# atmega2560_3_3v_8mhz.net
KiCad netlist of a schematic drawn in EAGLE
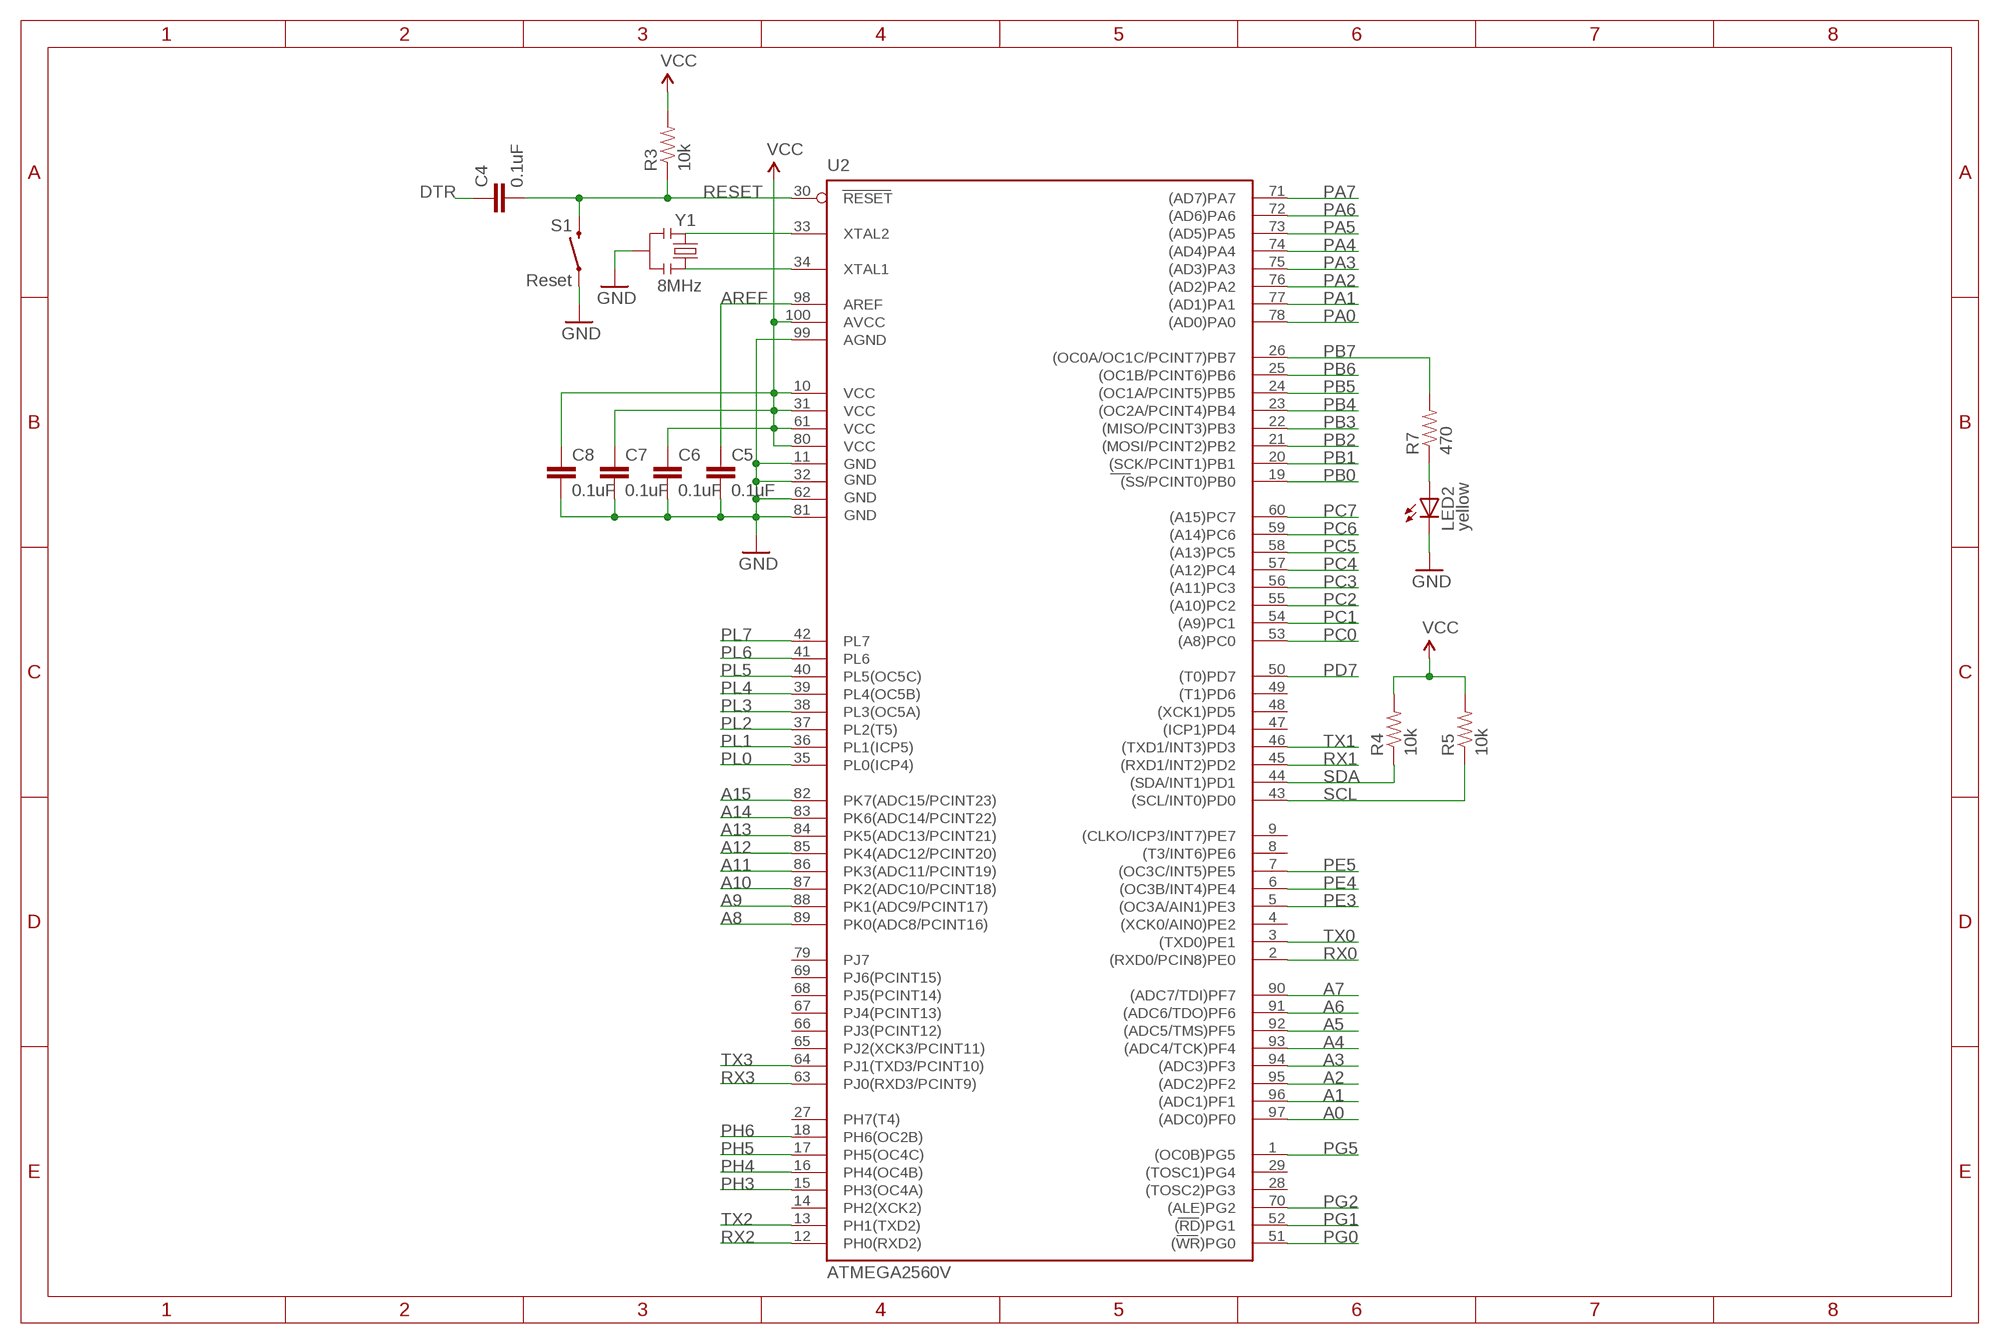
[diagram p0: schematic, sheet 1]

(export (version "E")
  (design (tool "Eeschema 10.0.6"))
  (components
    (comp (ref "C4")
      (value "0.1uF")
      (footprint "eagle-import:0402-CAP")
      (libsource (lib "eagle-import") (part "CAP0402-CAP"))
    )
    (comp (ref "C5")
      (value "0.1uF")
      (footprint "eagle-import:0402-CAP")
      (libsource (lib "eagle-import") (part "CAP0402-CAP"))
    )
    (comp (ref "C6")
      (value "0.1uF")
      (footprint "eagle-import:0402-CAP")
      (libsource (lib "eagle-import") (part "CAP0402-CAP"))
    )
    (comp (ref "C7")
      (value "0.1uF")
      (footprint "eagle-import:0402-CAP")
      (libsource (lib "eagle-import") (part "CAP0402-CAP"))
    )
    (comp (ref "C8")
      (value "0.1uF")
      (footprint "eagle-import:0402-CAP")
      (libsource (lib "eagle-import") (part "CAP0402-CAP"))
    )
    (comp (ref "LED2")
      (value "yellow")
      (footprint "eagle-import:LED-0603")
      (libsource (lib "eagle-import") (part "LED0603"))
    )
    (comp (ref "R3")
      (value "10k")
      (footprint "eagle-import:0402-RES")
      (libsource (lib "eagle-import") (part "RESISTOR0402-RES"))
    )
    (comp (ref "R4")
      (value "10k")
      (footprint "eagle-import:0402-RES")
      (libsource (lib "eagle-import") (part "RESISTOR0402-RES"))
    )
    (comp (ref "R5")
      (value "10k")
      (footprint "eagle-import:0402-RES")
      (libsource (lib "eagle-import") (part "RESISTOR0402-RES"))
    )
    (comp (ref "R7")
      (value "470")
      (footprint "eagle-import:0402-RES")
      (libsource (lib "eagle-import") (part "RESISTOR0402-RES"))
    )
    (comp (ref "S1")
      (value "SWITCH-MOMENTARY-2SMD")
      (footprint "eagle-import:TACTILE_SWITCH_SMD")
      (libsource (lib "eagle-import") (part "SWITCH-MOMENTARY-2SMD"))
    )
    (comp (ref "U2")
      (value "ATMEGA2560AU")
      (footprint "eagle-import:TQFP100")
      (libsource (lib "eagle-import") (part "ATMEGA2560AU"))
    )
    (comp (ref "Y1")
      (value "RESONATORSMD")
      (footprint "eagle-import:RESONATOR-SMD")
      (libsource (lib "eagle-import") (part "RESONATORSMD"))
    )
  )
  (nets
    (net (code "1") (name "/A0") (class "Default")
      (node (ref "U2") (pin "97") (pinfunction "(ADC0)PF0_97") (pintype "bidirectional"))
    )
    (net (code "2") (name "/A1") (class "Default")
      (node (ref "U2") (pin "96") (pinfunction "(ADC1)PF1_96") (pintype "bidirectional"))
    )
    (net (code "3") (name "/A2") (class "Default")
      (node (ref "U2") (pin "95") (pinfunction "(ADC2)PF2_95") (pintype "bidirectional"))
    )
    (net (code "4") (name "/A3") (class "Default")
      (node (ref "U2") (pin "94") (pinfunction "(ADC3)PF3_94") (pintype "bidirectional"))
    )
    (net (code "5") (name "/A4") (class "Default")
      (node (ref "U2") (pin "93") (pinfunction "(ADC4/TCK)PF4_93") (pintype "bidirectional"))
    )
    (net (code "6") (name "/A5") (class "Default")
      (node (ref "U2") (pin "92") (pinfunction "(ADC5/TMS)PF5_92") (pintype "bidirectional"))
    )
    (net (code "7") (name "/A6") (class "Default")
      (node (ref "U2") (pin "91") (pinfunction "(ADC6/TDO)PF6_91") (pintype "bidirectional"))
    )
    (net (code "8") (name "/A7") (class "Default")
      (node (ref "U2") (pin "90") (pinfunction "(ADC7/TDI)PF7_90") (pintype "bidirectional"))
    )
    (net (code "9") (name "/A8") (class "Default")
      (node (ref "U2") (pin "89") (pinfunction "PK0(ADC8/PCINT16)_89") (pintype "bidirectional"))
    )
    (net (code "10") (name "/A9") (class "Default")
      (node (ref "U2") (pin "88") (pinfunction "PK1(ADC9/PCINT17)_88") (pintype "bidirectional"))
    )
    (net (code "11") (name "/A10") (class "Default")
      (node (ref "U2") (pin "87") (pinfunction "PK2(ADC10/PCINT18)_87") (pintype "bidirectional"))
    )
    (net (code "12") (name "/A11") (class "Default")
      (node (ref "U2") (pin "86") (pinfunction "PK3(ADC11/PCINT19)_86") (pintype "bidirectional"))
    )
    (net (code "13") (name "/A12") (class "Default")
      (node (ref "U2") (pin "85") (pinfunction "PK4(ADC12/PCINT20)_85") (pintype "bidirectional"))
    )
    (net (code "14") (name "/A13") (class "Default")
      (node (ref "U2") (pin "84") (pinfunction "PK5(ADC13/PCINT21)_84") (pintype "bidirectional"))
    )
    (net (code "15") (name "/A14") (class "Default")
      (node (ref "U2") (pin "83") (pinfunction "PK6(ADC14/PCINT22)_83") (pintype "bidirectional"))
    )
    (net (code "16") (name "/A15") (class "Default")
      (node (ref "U2") (pin "82") (pinfunction "PK7(ADC15/PCINT23)_82") (pintype "bidirectional"))
    )
    (net (code "17") (name "/AREF") (class "Default")
      (node (ref "C5") (pin "1") (pinfunction "1_1") (pintype "passive"))
      (node (ref "U2") (pin "98") (pinfunction "AREF_98") (pintype "bidirectional"))
    )
    (net (code "18") (name "/DTR") (class "Default")
      (node (ref "C4") (pin "1") (pinfunction "1_1") (pintype "passive"))
    )
    (net (code "19") (name "/PA0") (class "Default")
      (node (ref "U2") (pin "78") (pinfunction "(AD0)PA0_78") (pintype "bidirectional"))
    )
    (net (code "20") (name "/PA1") (class "Default")
      (node (ref "U2") (pin "77") (pinfunction "(AD1)PA1_77") (pintype "bidirectional"))
    )
    (net (code "21") (name "/PA2") (class "Default")
      (node (ref "U2") (pin "76") (pinfunction "(AD2)PA2_76") (pintype "bidirectional"))
    )
    (net (code "22") (name "/PA3") (class "Default")
      (node (ref "U2") (pin "75") (pinfunction "(AD3)PA3_75") (pintype "bidirectional"))
    )
    (net (code "23") (name "/PA4") (class "Default")
      (node (ref "U2") (pin "74") (pinfunction "(AD4)PA4_74") (pintype "bidirectional"))
    )
    (net (code "24") (name "/PA5") (class "Default")
      (node (ref "U2") (pin "73") (pinfunction "(AD5)PA5_73") (pintype "bidirectional"))
    )
    (net (code "25") (name "/PA6") (class "Default")
      (node (ref "U2") (pin "72") (pinfunction "(AD6)PA6_72") (pintype "bidirectional"))
    )
    (net (code "26") (name "/PA7") (class "Default")
      (node (ref "U2") (pin "71") (pinfunction "(AD7)PA7_71") (pintype "bidirectional"))
    )
    (net (code "27") (name "/PB0") (class "Default")
      (node (ref "U2") (pin "19") (pinfunction "(SS/PCINT0)PB0_19") (pintype "bidirectional"))
    )
    (net (code "28") (name "/PB1") (class "Default")
      (node (ref "U2") (pin "20") (pinfunction "(SCK/PCINT1)PB1_20") (pintype "bidirectional"))
    )
    (net (code "29") (name "/PB2") (class "Default")
      (node (ref "U2") (pin "21") (pinfunction "(MOSI/PCINT2)PB2_21") (pintype "bidirectional"))
    )
    (net (code "30") (name "/PB3") (class "Default")
      (node (ref "U2") (pin "22") (pinfunction "(MISO/PCINT3)PB3_22") (pintype "bidirectional"))
    )
    (net (code "31") (name "/PB4") (class "Default")
      (node (ref "U2") (pin "23") (pinfunction "(OC2A/PCINT4)PB4_23") (pintype "bidirectional"))
    )
    (net (code "32") (name "/PB5") (class "Default")
      (node (ref "U2") (pin "24") (pinfunction "(OC1A/PCINT5)PB5_24") (pintype "bidirectional"))
    )
    (net (code "33") (name "/PB6") (class "Default")
      (node (ref "U2") (pin "25") (pinfunction "(OC1B/PCINT6)PB6_25") (pintype "bidirectional"))
    )
    (net (code "34") (name "/PB7") (class "Default")
      (node (ref "R7") (pin "2") (pinfunction "2_2") (pintype "passive"))
      (node (ref "U2") (pin "26") (pinfunction "(OC0A/OC1C/PCINT7)PB7_26") (pintype "bidirectional"))
    )
    (net (code "35") (name "/PC0") (class "Default")
      (node (ref "U2") (pin "53") (pinfunction "(A8)PC0_53") (pintype "bidirectional"))
    )
    (net (code "36") (name "/PC1") (class "Default")
      (node (ref "U2") (pin "54") (pinfunction "(A9)PC1_54") (pintype "bidirectional"))
    )
    (net (code "37") (name "/PC2") (class "Default")
      (node (ref "U2") (pin "55") (pinfunction "(A10)PC2_55") (pintype "bidirectional"))
    )
    (net (code "38") (name "/PC3") (class "Default")
      (node (ref "U2") (pin "56") (pinfunction "(A11)PC3_56") (pintype "bidirectional"))
    )
    (net (code "39") (name "/PC4") (class "Default")
      (node (ref "U2") (pin "57") (pinfunction "(A12)PC4_57") (pintype "bidirectional"))
    )
    (net (code "40") (name "/PC5") (class "Default")
      (node (ref "U2") (pin "58") (pinfunction "(A13)PC5_58") (pintype "bidirectional"))
    )
    (net (code "41") (name "/PC6") (class "Default")
      (node (ref "U2") (pin "59") (pinfunction "(A14)PC6_59") (pintype "bidirectional"))
    )
    (net (code "42") (name "/PC7") (class "Default")
      (node (ref "U2") (pin "60") (pinfunction "(A15)PC7_60") (pintype "bidirectional"))
    )
    (net (code "43") (name "/PD7") (class "Default")
      (node (ref "U2") (pin "50") (pinfunction "(T0)PD7_50") (pintype "bidirectional"))
    )
    (net (code "44") (name "/PE3") (class "Default")
      (node (ref "U2") (pin "5") (pinfunction "(OC3A/AIN1)PE3_5") (pintype "bidirectional"))
    )
    (net (code "45") (name "/PE4") (class "Default")
      (node (ref "U2") (pin "6") (pinfunction "(OC3B/INT4)PE4_6") (pintype "bidirectional"))
    )
    (net (code "46") (name "/PE5") (class "Default")
      (node (ref "U2") (pin "7") (pinfunction "(OC3C/INT5)PE5_7") (pintype "bidirectional"))
    )
    (net (code "47") (name "/PG0") (class "Default")
      (node (ref "U2") (pin "51") (pinfunction "(WR)PG0_51") (pintype "bidirectional"))
    )
    (net (code "48") (name "/PG1") (class "Default")
      (node (ref "U2") (pin "52") (pinfunction "(RD)PG1_52") (pintype "bidirectional"))
    )
    (net (code "49") (name "/PG2") (class "Default")
      (node (ref "U2") (pin "70") (pinfunction "(ALE)PG2_70") (pintype "bidirectional"))
    )
    (net (code "50") (name "/PG5") (class "Default")
      (node (ref "U2") (pin "1") (pinfunction "(OC0B)PG5_1") (pintype "bidirectional"))
    )
    (net (code "51") (name "/PH3") (class "Default")
      (node (ref "U2") (pin "15") (pinfunction "PH3(OC4A)_15") (pintype "bidirectional"))
    )
    (net (code "52") (name "/PH4") (class "Default")
      (node (ref "U2") (pin "16") (pinfunction "PH4(OC4B)_16") (pintype "bidirectional"))
    )
    (net (code "53") (name "/PH5") (class "Default")
      (node (ref "U2") (pin "17") (pinfunction "PH5(OC4C)_17") (pintype "bidirectional"))
    )
    (net (code "54") (name "/PH6") (class "Default")
      (node (ref "U2") (pin "18") (pinfunction "PH6(OC2B)_18") (pintype "bidirectional"))
    )
    (net (code "55") (name "/PL0") (class "Default")
      (node (ref "U2") (pin "35") (pinfunction "PL0(ICP4)_35") (pintype "bidirectional"))
    )
    (net (code "56") (name "/PL1") (class "Default")
      (node (ref "U2") (pin "36") (pinfunction "PL1(ICP5)_36") (pintype "bidirectional"))
    )
    (net (code "57") (name "/PL2") (class "Default")
      (node (ref "U2") (pin "37") (pinfunction "PL2(T5)_37") (pintype "bidirectional"))
    )
    (net (code "58") (name "/PL3") (class "Default")
      (node (ref "U2") (pin "38") (pinfunction "PL3(OC5A)_38") (pintype "bidirectional"))
    )
    (net (code "59") (name "/PL4") (class "Default")
      (node (ref "U2") (pin "39") (pinfunction "PL4(OC5B)_39") (pintype "bidirectional"))
    )
    (net (code "60") (name "/PL5") (class "Default")
      (node (ref "U2") (pin "40") (pinfunction "PL5(OC5C)_40") (pintype "bidirectional"))
    )
    (net (code "61") (name "/PL6") (class "Default")
      (node (ref "U2") (pin "41") (pinfunction "PL6_41") (pintype "bidirectional"))
    )
    (net (code "62") (name "/PL7") (class "Default")
      (node (ref "U2") (pin "42") (pinfunction "PL7_42") (pintype "bidirectional"))
    )
    (net (code "63") (name "/RESET") (class "Default")
      (node (ref "C4") (pin "2") (pinfunction "2_2") (pintype "passive"))
      (node (ref "R3") (pin "1") (pinfunction "1_1") (pintype "passive"))
      (node (ref "S1") (pin "3") (pinfunction "2_3") (pintype "passive"))
      (node (ref "U2") (pin "30") (pinfunction "RESET_30") (pintype "input"))
    )
    (net (code "64") (name "/RX0") (class "Default")
      (node (ref "U2") (pin "2") (pinfunction "(RXD0/PCIN8)PE0_2") (pintype "bidirectional"))
    )
    (net (code "65") (name "/RX1") (class "Default")
      (node (ref "U2") (pin "45") (pinfunction "(RXD1/INT2)PD2_45") (pintype "bidirectional"))
    )
    (net (code "66") (name "/RX2") (class "Default")
      (node (ref "U2") (pin "12") (pinfunction "PH0(RXD2)_12") (pintype "bidirectional"))
    )
    (net (code "67") (name "/RX3") (class "Default")
      (node (ref "U2") (pin "63") (pinfunction "PJ0(RXD3/PCINT9)_63") (pintype "bidirectional"))
    )
    (net (code "68") (name "/SCL") (class "Default")
      (node (ref "R5") (pin "1") (pinfunction "1_1") (pintype "passive"))
      (node (ref "U2") (pin "43") (pinfunction "(SCL/INT0)PD0_43") (pintype "bidirectional"))
    )
    (net (code "69") (name "/SDA") (class "Default")
      (node (ref "R4") (pin "1") (pinfunction "1_1") (pintype "passive"))
      (node (ref "U2") (pin "44") (pinfunction "(SDA/INT1)PD1_44") (pintype "bidirectional"))
    )
    (net (code "70") (name "/TX0") (class "Default")
      (node (ref "U2") (pin "3") (pinfunction "(TXD0)PE1_3") (pintype "bidirectional"))
    )
    (net (code "71") (name "/TX1") (class "Default")
      (node (ref "U2") (pin "46") (pinfunction "(TXD1/INT3)PD3_46") (pintype "bidirectional"))
    )
    (net (code "72") (name "/TX2") (class "Default")
      (node (ref "U2") (pin "13") (pinfunction "PH1(TXD2)_13") (pintype "bidirectional"))
    )
    (net (code "73") (name "/TX3") (class "Default")
      (node (ref "U2") (pin "64") (pinfunction "PJ1(TXD3/PCINT10)_64") (pintype "bidirectional"))
    )
    (net (code "74") (name "GND") (class "Default")
      (node (ref "C5") (pin "2") (pinfunction "2_2") (pintype "passive"))
      (node (ref "C6") (pin "2") (pinfunction "2_2") (pintype "passive"))
      (node (ref "C7") (pin "2") (pinfunction "2_2") (pintype "passive"))
      (node (ref "C8") (pin "2") (pinfunction "2_2") (pintype "passive"))
      (node (ref "LED2") (pin "C") (pinfunction "C_C") (pintype "passive"))
      (node (ref "S1") (pin "1") (pinfunction "1_1") (pintype "passive"))
      (node (ref "U2") (pin "11") (pinfunction "GND_11") (pintype "power_in"))
      (node (ref "U2") (pin "32") (pinfunction "GND1_32") (pintype "power_in"))
      (node (ref "U2") (pin "62") (pinfunction "GND2_62") (pintype "power_in"))
      (node (ref "U2") (pin "81") (pinfunction "GND3_81") (pintype "power_in"))
      (node (ref "U2") (pin "99") (pinfunction "AGND_99") (pintype "power_in"))
      (node (ref "Y1") (pin "2") (pinfunction "2_2") (pintype "passive"))
    )
    (net (code "75") (name "Net-(LED2-PadA)") (class "Default")
      (node (ref "LED2") (pin "A") (pinfunction "A_A") (pintype "passive"))
      (node (ref "R7") (pin "1") (pinfunction "1_1") (pintype "passive"))
    )
    (net (code "76") (name "Net-(U2-XTAL1)") (class "Default")
      (node (ref "U2") (pin "34") (pinfunction "XTAL1_34") (pintype "input"))
      (node (ref "Y1") (pin "3") (pinfunction "3_3") (pintype "passive"))
    )
    (net (code "77") (name "Net-(U2-XTAL2)") (class "Default")
      (node (ref "U2") (pin "33") (pinfunction "XTAL2_33") (pintype "output"))
      (node (ref "Y1") (pin "1") (pinfunction "1_1") (pintype "passive"))
    )
    (net (code "78") (name "VCC") (class "Default")
      (node (ref "C6") (pin "1") (pinfunction "1_1") (pintype "passive"))
      (node (ref "C7") (pin "1") (pinfunction "1_1") (pintype "passive"))
      (node (ref "C8") (pin "1") (pinfunction "1_1") (pintype "passive"))
      (node (ref "R3") (pin "2") (pinfunction "2_2") (pintype "passive"))
      (node (ref "R4") (pin "2") (pinfunction "2_2") (pintype "passive"))
      (node (ref "R5") (pin "2") (pinfunction "2_2") (pintype "passive"))
      (node (ref "U2") (pin "10") (pinfunction "VCC_10") (pintype "power_in"))
      (node (ref "U2") (pin "100") (pinfunction "AVCC_100") (pintype "power_in"))
      (node (ref "U2") (pin "31") (pinfunction "VCC1_31") (pintype "power_in"))
      (node (ref "U2") (pin "61") (pinfunction "VCC2_61") (pintype "power_in"))
      (node (ref "U2") (pin "80") (pinfunction "VCC3_80") (pintype "power_in"))
    )
    (net (code "79") (name "unconnected-(U2-(CLKO{slash}ICP3{slash}INT7)PE7-Pad9)") (class "Default")
      (node (ref "U2") (pin "9") (pinfunction "(CLKO/ICP3/INT7)PE7_9") (pintype "bidirectional"))
    )
    (net (code "80") (name "unconnected-(U2-(ICP1)PD4-Pad47)") (class "Default")
      (node (ref "U2") (pin "47") (pinfunction "(ICP1)PD4_47") (pintype "bidirectional"))
    )
    (net (code "81") (name "unconnected-(U2-(T1)PD6-Pad49)") (class "Default")
      (node (ref "U2") (pin "49") (pinfunction "(T1)PD6_49") (pintype "bidirectional"))
    )
    (net (code "82") (name "unconnected-(U2-(T3{slash}INT6)PE6-Pad8)") (class "Default")
      (node (ref "U2") (pin "8") (pinfunction "(T3/INT6)PE6_8") (pintype "bidirectional"))
    )
    (net (code "83") (name "unconnected-(U2-(TOSC1)PG4-Pad29)") (class "Default")
      (node (ref "U2") (pin "29") (pinfunction "(TOSC1)PG4_29") (pintype "bidirectional"))
    )
    (net (code "84") (name "unconnected-(U2-(TOSC2)PG3-Pad28)") (class "Default")
      (node (ref "U2") (pin "28") (pinfunction "(TOSC2)PG3_28") (pintype "bidirectional"))
    )
    (net (code "85") (name "unconnected-(U2-(XCK0{slash}AIN0)PE2-Pad4)") (class "Default")
      (node (ref "U2") (pin "4") (pinfunction "(XCK0/AIN0)PE2_4") (pintype "bidirectional"))
    )
    (net (code "86") (name "unconnected-(U2-(XCK1)PD5-Pad48)") (class "Default")
      (node (ref "U2") (pin "48") (pinfunction "(XCK1)PD5_48") (pintype "bidirectional"))
    )
    (net (code "87") (name "unconnected-(U2-PH2(XCK2)-Pad14)") (class "Default")
      (node (ref "U2") (pin "14") (pinfunction "PH2(XCK2)_14") (pintype "bidirectional"))
    )
    (net (code "88") (name "unconnected-(U2-PH7(T4)-Pad27)") (class "Default")
      (node (ref "U2") (pin "27") (pinfunction "PH7(T4)_27") (pintype "bidirectional"))
    )
    (net (code "89") (name "unconnected-(U2-PJ2(XCK3{slash}PCINT11)-Pad65)") (class "Default")
      (node (ref "U2") (pin "65") (pinfunction "PJ2(XCK3/PCINT11)_65") (pintype "bidirectional"))
    )
    (net (code "90") (name "unconnected-(U2-PJ3(PCINT12)-Pad66)") (class "Default")
      (node (ref "U2") (pin "66") (pinfunction "PJ3(PCINT12)_66") (pintype "bidirectional"))
    )
    (net (code "91") (name "unconnected-(U2-PJ4(PCINT13)-Pad67)") (class "Default")
      (node (ref "U2") (pin "67") (pinfunction "PJ4(PCINT13)_67") (pintype "bidirectional"))
    )
    (net (code "92") (name "unconnected-(U2-PJ5(PCINT14)-Pad68)") (class "Default")
      (node (ref "U2") (pin "68") (pinfunction "PJ5(PCINT14)_68") (pintype "bidirectional"))
    )
    (net (code "93") (name "unconnected-(U2-PJ6(PCINT15)-Pad69)") (class "Default")
      (node (ref "U2") (pin "69") (pinfunction "PJ6(PCINT15)_69") (pintype "bidirectional"))
    )
    (net (code "94") (name "unconnected-(U2-PJ7-Pad79)") (class "Default")
      (node (ref "U2") (pin "79") (pinfunction "PJ7_79") (pintype "bidirectional"))
    )
  )
)
